# MOFO_v1.net
KiCad netlist of a schematic drawn in EAGLE
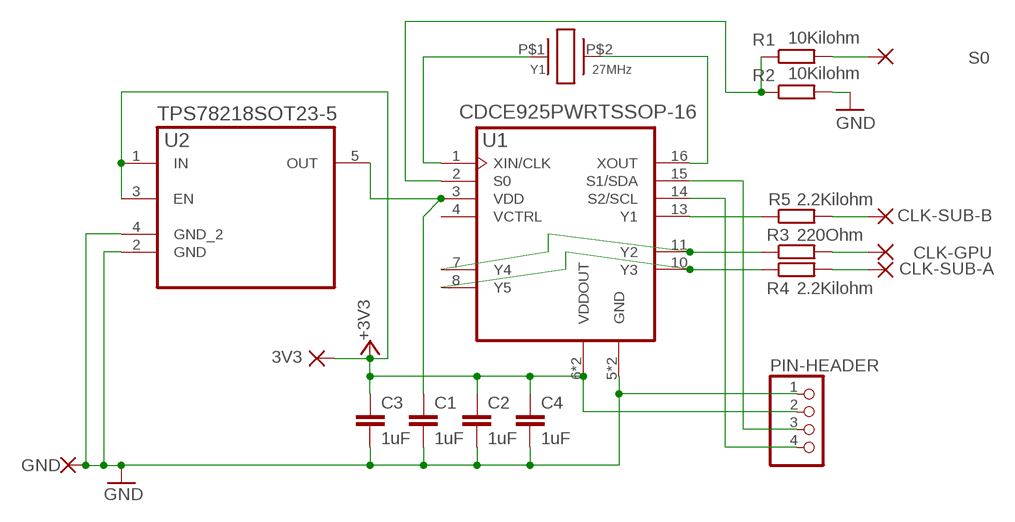
[diagram p0: schematic, sheet 1]

(export (version "E")
  (design (tool "Eeschema 10.0.6"))
  (components
    (comp (ref "3V3")
      (value "PADSCIRCLE-1,5X1,5")
      (footprint "eagle-import:CIRCLE-1,5X1,5")
      (libsource (lib "eagle-import") (part "PADSCIRCLE-1,5X1,5"))
    )
    (comp (ref "C1")
      (value "1uF")
      (footprint "eagle-import:C0603")
      (libsource (lib "eagle-import") (part "CAPACITORSC0603"))
    )
    (comp (ref "C2")
      (value "1uF")
      (footprint "eagle-import:C0603")
      (libsource (lib "eagle-import") (part "CAPACITORSC0603"))
    )
    (comp (ref "C3")
      (value "1uF")
      (footprint "eagle-import:C0603")
      (libsource (lib "eagle-import") (part "CAPACITORSC0603"))
    )
    (comp (ref "C4")
      (value "1uF")
      (footprint "eagle-import:C0603")
      (libsource (lib "eagle-import") (part "CAPACITORSC0603"))
    )
    (comp (ref "CLK-GPU")
      (value "PADSCIRCLE-1,5X1,5")
      (footprint "eagle-import:CIRCLE-1,5X1,5")
      (libsource (lib "eagle-import") (part "PADSCIRCLE-1,5X1,5"))
    )
    (comp (ref "CLK-SUB-A")
      (value "PADSCIRCLE-1,5X1,5")
      (footprint "eagle-import:CIRCLE-1,5X1,5")
      (libsource (lib "eagle-import") (part "PADSCIRCLE-1,5X1,5"))
    )
    (comp (ref "CLK-SUB-B")
      (value "PADSCIRCLE-1,5X1,5")
      (footprint "eagle-import:CIRCLE-1,5X1,5")
      (libsource (lib "eagle-import") (part "PADSCIRCLE-1,5X1,5"))
    )
    (comp (ref "GND")
      (value "PADSCIRCLE-1,5X1,5")
      (footprint "eagle-import:CIRCLE-1,5X1,5")
      (libsource (lib "eagle-import") (part "PADSCIRCLE-1,5X1,5"))
    )
    (comp (ref "PIN-HEADER")
      (value "PIN-HEADER-1X4PH-1X04M")
      (footprint "eagle-import:PH-1X04M")
      (libsource (lib "eagle-import") (part "PIN-HEADER-1X4PH-1X04M"))
    )
    (comp (ref "R1")
      (value "10Kilohm")
      (footprint "eagle-import:R0603")
      (libsource (lib "eagle-import") (part "RESISTORSR0603"))
    )
    (comp (ref "R2")
      (value "10Kilohm")
      (footprint "eagle-import:R0603")
      (libsource (lib "eagle-import") (part "RESISTORSR0603"))
    )
    (comp (ref "R3")
      (value "220Ohm")
      (footprint "eagle-import:R0603")
      (libsource (lib "eagle-import") (part "RESISTORSR0603"))
    )
    (comp (ref "R4")
      (value "2.2Kilohm")
      (footprint "eagle-import:R0603")
      (libsource (lib "eagle-import") (part "RESISTORSR0603"))
    )
    (comp (ref "R5")
      (value "2.2Kilohm")
      (footprint "eagle-import:R0603")
      (libsource (lib "eagle-import") (part "RESISTORSR0603"))
    )
    (comp (ref "S0")
      (value "PADSCIRCLE-1,5X1,5")
      (footprint "eagle-import:CIRCLE-1,5X1,5")
      (libsource (lib "eagle-import") (part "PADSCIRCLE-1,5X1,5"))
    )
    (comp (ref "U1")
      (value "CDCE925PWRTSSOP-16")
      (footprint "eagle-import:TSSOP-16")
      (libsource (lib "eagle-import") (part "CDCE925PWRTSSOP-16"))
    )
    (comp (ref "U2")
      (value "TPS78218SOT23-5")
      (footprint "eagle-import:SOT23-5")
      (libsource (lib "eagle-import") (part "TPS78218SOT23-5"))
    )
    (comp (ref "Y1")
      (value "27MHz")
      (footprint "eagle-import:ABM3")
      (libsource (lib "eagle-import") (part "ABM3ABM3"))
    )
  )
  (nets
    (net (code "1") (name "+3V3") (class "Default")
      (node (ref "3V3") (pin "1") (pinfunction "P_1") (pintype "passive"))
      (node (ref "C2") (pin "1") (pinfunction "1_1") (pintype "passive"))
      (node (ref "C3") (pin "1") (pinfunction "1_1") (pintype "passive"))
      (node (ref "C4") (pin "1") (pinfunction "1_1") (pintype "passive"))
      (node (ref "PIN-HEADER") (pin "2") (pinfunction "2_2") (pintype "passive"))
      (node (ref "U1") (pin "6") (pinfunction "VDDOUT_6") (pintype "power_in"))
      (node (ref "U1") (pin "9") (pinfunction "VDDOUT_9") (pintype "power_in"))
      (node (ref "U2") (pin "1") (pinfunction "IN_1") (pintype "input"))
      (node (ref "U2") (pin "3") (pinfunction "EN_3") (pintype "input"))
    )
    (net (code "2") (name "GND") (class "Default")
      (node (ref "C1") (pin "2") (pinfunction "2_2") (pintype "passive"))
      (node (ref "C2") (pin "2") (pinfunction "2_2") (pintype "passive"))
      (node (ref "C3") (pin "2") (pinfunction "2_2") (pintype "passive"))
      (node (ref "C4") (pin "2") (pinfunction "2_2") (pintype "passive"))
      (node (ref "GND") (pin "1") (pinfunction "P_1") (pintype "passive"))
      (node (ref "PIN-HEADER") (pin "1") (pinfunction "1_1") (pintype "passive"))
      (node (ref "R2") (pin "2") (pinfunction "2_2") (pintype "passive"))
      (node (ref "U1") (pin "12") (pinfunction "GND_12") (pintype "power_in"))
      (node (ref "U1") (pin "5") (pinfunction "GND_5") (pintype "power_in"))
      (node (ref "U2") (pin "2") (pinfunction "GND_2") (pintype "passive"))
      (node (ref "U2") (pin "4") (pinfunction "GND_2_4") (pintype "passive"))
    )
    (net (code "3") (name "Net-(CLK-GPU-P)") (class "Default")
      (node (ref "CLK-GPU") (pin "1") (pinfunction "P_1") (pintype "passive"))
      (node (ref "R3") (pin "2") (pinfunction "2_2") (pintype "passive"))
    )
    (net (code "4") (name "Net-(CLK-SUB-A-P)") (class "Default")
      (node (ref "CLK-SUB-A") (pin "1") (pinfunction "P_1") (pintype "passive"))
      (node (ref "R4") (pin "2") (pinfunction "2_2") (pintype "passive"))
    )
    (net (code "5") (name "Net-(CLK-SUB-B-P)") (class "Default")
      (node (ref "CLK-SUB-B") (pin "1") (pinfunction "P_1") (pintype "passive"))
      (node (ref "R5") (pin "2") (pinfunction "2_2") (pintype "passive"))
    )
    (net (code "6") (name "Net-(S0-P)") (class "Default")
      (node (ref "R1") (pin "2") (pinfunction "2_2") (pintype "passive"))
      (node (ref "S0") (pin "1") (pinfunction "P_1") (pintype "passive"))
    )
    (net (code "7") (name "Net-(U1-S0)") (class "Default")
      (node (ref "R1") (pin "1") (pinfunction "1_1") (pintype "passive"))
      (node (ref "R2") (pin "1") (pinfunction "1_1") (pintype "passive"))
      (node (ref "U1") (pin "2") (pinfunction "S0_2") (pintype "input"))
    )
    (net (code "8") (name "Net-(U1-S1{slash}SDA)") (class "Default")
      (node (ref "PIN-HEADER") (pin "3") (pinfunction "3_3") (pintype "passive"))
      (node (ref "U1") (pin "15") (pinfunction "S1/SDA_15") (pintype "bidirectional"))
    )
    (net (code "9") (name "Net-(U1-S2{slash}SCL)") (class "Default")
      (node (ref "PIN-HEADER") (pin "4") (pinfunction "4_4") (pintype "passive"))
      (node (ref "U1") (pin "14") (pinfunction "S2/SCL_14") (pintype "input"))
    )
    (net (code "10") (name "Net-(U1-VDD)") (class "Default")
      (node (ref "C1") (pin "1") (pinfunction "1_1") (pintype "passive"))
      (node (ref "U1") (pin "3") (pinfunction "VDD_3") (pintype "power_in"))
      (node (ref "U2") (pin "5") (pinfunction "OUT_5") (pintype "output"))
    )
    (net (code "11") (name "Net-(U1-XIN{slash}CLK)") (class "Default")
      (node (ref "U1") (pin "1") (pinfunction "XIN/CLK_1") (pintype "input"))
      (node (ref "Y1") (pin "P$1") (pinfunction "1_P$1") (pintype "bidirectional"))
    )
    (net (code "12") (name "Net-(U1-XOUT)") (class "Default")
      (node (ref "U1") (pin "16") (pinfunction "XOUT_16") (pintype "output"))
      (node (ref "Y1") (pin "P$2") (pinfunction "2_P$2") (pintype "bidirectional"))
    )
    (net (code "13") (name "Net-(U1-Y1)") (class "Default")
      (node (ref "R5") (pin "1") (pinfunction "1_1") (pintype "passive"))
      (node (ref "U1") (pin "13") (pinfunction "Y1_13") (pintype "output"))
    )
    (net (code "14") (name "Net-(U1-Y2)") (class "Default")
      (node (ref "R3") (pin "1") (pinfunction "1_1") (pintype "passive"))
      (node (ref "U1") (pin "11") (pinfunction "Y2_11") (pintype "output"))
      (node (ref "U1") (pin "7") (pinfunction "Y4_7") (pintype "output"))
    )
    (net (code "15") (name "Net-(U1-Y3)") (class "Default")
      (node (ref "R4") (pin "1") (pinfunction "1_1") (pintype "passive"))
      (node (ref "U1") (pin "10") (pinfunction "Y3_10") (pintype "output"))
      (node (ref "U1") (pin "8") (pinfunction "Y5_8") (pintype "output"))
    )
    (net (code "16") (name "unconnected-(U1-VCTRL-Pad4)") (class "Default")
      (node (ref "U1") (pin "4") (pinfunction "VCTRL_4") (pintype "input"))
    )
  )
)
